# SUPPLY_IN.net
KiCad netlist of a schematic drawn in Altium Designer
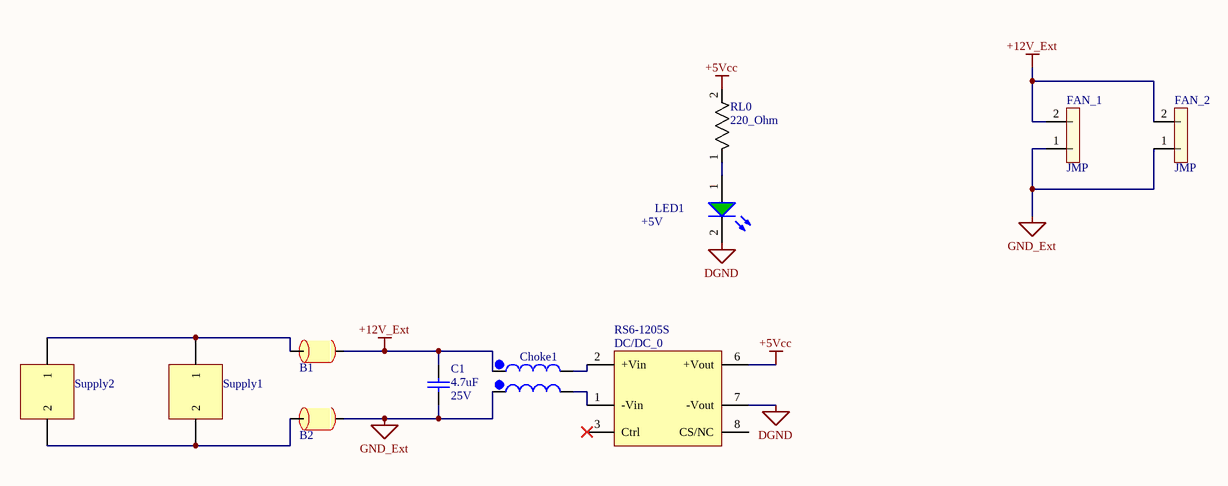
[diagram p0: SUPPLY_IN.SchDoc]

(export (version "E")
  (design (tool "Eeschema 10.0.6"))
  (components
    (comp (ref "B1")
      (value "Bead")
      (footprint "RES_1206")
      (description "FERRITE BEAD 60 OHM 1206 1LN")
      (fields (field (name "DIGI-KEY PART NUMBER") "587-1770-1-ND"))
      (libsource (lib "aislados") (part "Bead"))
    )
    (comp (ref "B2")
      (value "Bead")
      (footprint "RES_1206")
      (description "FERRITE BEAD 60 OHM 1206 1LN")
      (fields (field (name "DIGI-KEY PART NUMBER") "587-1770-1-ND"))
      (libsource (lib "aislados") (part "Bead"))
    )
    (comp (ref "C1")
      (value "4.7uF")
      (footprint "CAP_0805")
      (description "Capacitor")
      (fields (field (name "VOLTAGE") "25V"))
      (libsource (lib "Componentes_SOC") (part "Cap_0805"))
    )
    (comp (ref "Choke1")
      (value "~")
      (footprint "Choque SMD")
      (description "1.5A")
      (libsource (lib "Componentes_SOC") (part "Choque bourns SMD"))
    )
    (comp (ref "DC/DC_0")
      (value "RS6-1205S")
      (footprint "DC/DC SIP-8")
      (description "DC DC CONVERTER 5V 6W")
      (fields (field (name "DIGI-KEY PART NUMBER") "945-2984-ND"))
      (libsource (lib "aislados") (part "DC/DC SIP-8 1Output"))
    )
    (comp (ref "FAN_1")
      (value "JMP")
      (footprint "Terminal Block 2 pos 8A")
      (description "TERM BLOCK 2POS SIDE ENT 2.54MM / FAN AXIAL 40X15MM 12VDC WIRE")
      (fields (field (name "DIGI-KEY PART NUMBER") "277-1764-ND"))
      (libsource (lib "aislados") (part "jumper2pos"))
    )
    (comp (ref "FAN_2")
      (value "JMP")
      (footprint "Terminal Block 2 pos 8A")
      (description "TERM BLOCK 2POS SIDE ENT 2.54MM / FAN AXIAL 40X15MM 12VDC WIRE")
      (fields (field (name "DIGI-KEY PART NUMBER") "277-1764-ND"))
      (libsource (lib "aislados") (part "jumper2pos"))
    )
    (comp (ref "LED1")
      (value "+5V")
      (footprint "LED_0805")
      (description "LED BLUE CLEAR 0805 SMD")
      (fields
        (field (name "DIGI-KEY PART NUMBER") "732-4982-1-ND")
        (field (name "MANUFACTURER PART NUMBER") "150080BS75000")
      )
      (libsource (lib "WL-SMCW_rev15b") (part "WL-SMCW 0805  150080GS75000"))
    )
    (comp (ref "RL0")
      (value "220_Ohm")
      (footprint "res_0805")
      (description "1% 1/4W 0805")
      (fields
        (field (name "DIGI-KEY PART NUMBER") "311-220HRCT-ND")
        (field (name "MANUFACTURER PART NUMBER") "RC0603FR-07220RL")
      )
      (libsource (lib "RES470_ERJ-3GEYJ471V") (part "RES_ERJ-3GEYJ471V"))
    )
    (comp (ref "Supply1")
      (value "649006227222_1X2")
      (footprint "Conector tipo ATX Wurth 2 posiciones angulo recto")
      (fields
        (field (name "DIGI-KEY PART NUMBER") "732-1937-ND")
        (field (name "MANUFACTURER PART NUMBER") "649002227222")
      )
      (libsource (lib "aislados") (part "649006227222_1X2"))
    )
    (comp (ref "Supply2")
      (value "649006227222_1X2")
      (footprint "Conector tipo ATX Wurth 2 posiciones angulo recto")
      (fields
        (field (name "DIGI-KEY PART NUMBER") "732-1937-ND")
        (field (name "MANUFACTURER PART NUMBER") "649002227222")
      )
      (libsource (lib "aislados") (part "649006227222_1X2"))
    )
  )
  (nets
    (net (code "1") (name "+5Vcc") (class "Default")
      (node (ref "DC/DC_0") (pin "6") (pinfunction "+Vout_6") (pintype "passive"))
      (node (ref "RL0") (pin "2") (pinfunction "A_2") (pintype "passive"))
    )
    (net (code "2") (name "+12V_Ext") (class "Default")
      (node (ref "B1") (pin "2") (pintype "passive"))
      (node (ref "C1") (pin "1") (pinfunction "1_1") (pintype "passive"))
      (node (ref "Choke1") (pin "1") (pinfunction "1_1") (pintype "passive"))
      (node (ref "FAN_1") (pin "2") (pinfunction "2_2") (pintype "passive"))
      (node (ref "FAN_2") (pin "2") (pinfunction "2_2") (pintype "passive"))
    )
    (net (code "3") (name "DGND") (class "Default")
      (node (ref "DC/DC_0") (pin "7") (pinfunction "-Vout_7") (pintype "passive"))
      (node (ref "LED1") (pin "2") (pinfunction "C_2") (pintype "passive"))
    )
    (net (code "4") (name "GND_Ext") (class "Default")
      (node (ref "B2") (pin "2") (pintype "passive"))
      (node (ref "C1") (pin "2") (pinfunction "2_2") (pintype "passive"))
      (node (ref "Choke1") (pin "4") (pinfunction "4_4") (pintype "passive"))
      (node (ref "FAN_1") (pin "1") (pinfunction "1_1") (pintype "passive"))
      (node (ref "FAN_2") (pin "1") (pinfunction "1_1") (pintype "passive"))
    )
    (net (code "5") (name "Net-(B1-Pad1)") (class "Default")
      (node (ref "B1") (pin "1") (pintype "passive"))
      (node (ref "Supply1") (pin "1") (pinfunction "1_1") (pintype "passive"))
      (node (ref "Supply2") (pin "1") (pinfunction "1_1") (pintype "passive"))
    )
    (net (code "6") (name "Net-(B2-Pad1)") (class "Default")
      (node (ref "B2") (pin "1") (pintype "passive"))
      (node (ref "Supply1") (pin "2") (pinfunction "2_2") (pintype "passive"))
      (node (ref "Supply2") (pin "2") (pinfunction "2_2") (pintype "passive"))
    )
    (net (code "7") (name "Net-(DC/DC_0-+Vin)") (class "Default")
      (node (ref "Choke1") (pin "2") (pinfunction "2_2") (pintype "passive"))
      (node (ref "DC/DC_0") (pin "2") (pinfunction "+Vin_2") (pintype "passive"))
    )
    (net (code "8") (name "Net-(DC/DC_0--Vin)") (class "Default")
      (node (ref "Choke1") (pin "3") (pinfunction "3_3") (pintype "passive"))
      (node (ref "DC/DC_0") (pin "1") (pinfunction "-Vin_1") (pintype "passive"))
    )
    (net (code "9") (name "Net-(LED1-A)") (class "Default")
      (node (ref "LED1") (pin "1") (pinfunction "A_1") (pintype "passive"))
      (node (ref "RL0") (pin "1") (pinfunction "C_1") (pintype "passive"))
    )
    (net (code "10") (name "unconnected-(DC/DC_0-CS{slash}NC-Pad8)") (class "Default")
      (node (ref "DC/DC_0") (pin "8") (pinfunction "CS/NC_8") (pintype "passive"))
    )
    (net (code "11") (name "unconnected-(DC/DC_0-Ctrl-Pad3)") (class "Default")
      (node (ref "DC/DC_0") (pin "3") (pinfunction "Ctrl_3") (pintype "passive+no_connect"))
    )
  )
)
